# GasSensor.net
KiCad netlist of a schematic drawn in Altium Designer
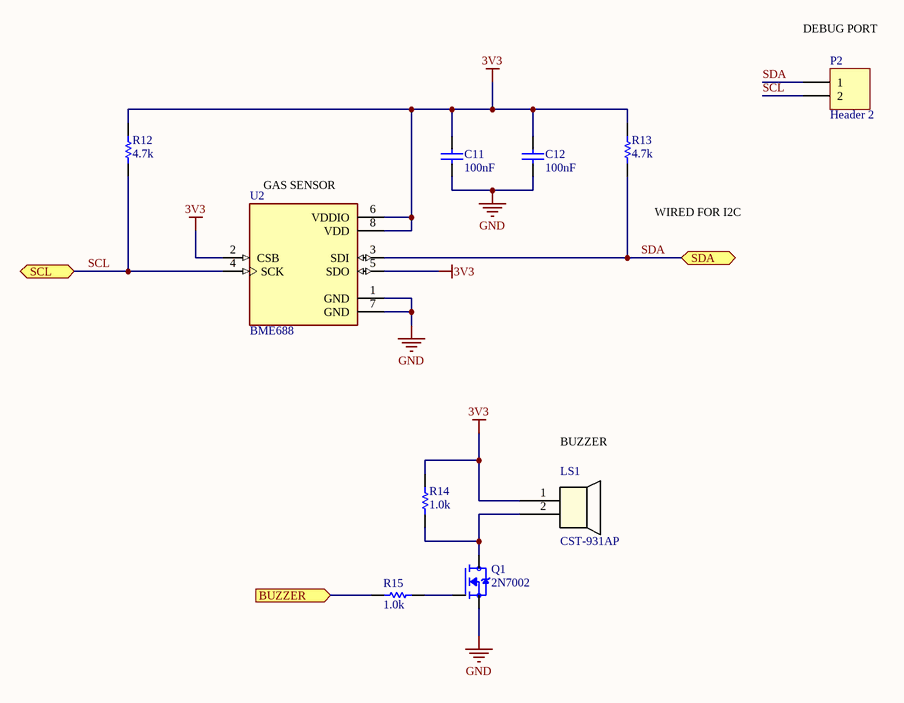
[diagram p0: GasSensor.SchDoc]

(export (version "E")
  (design (tool "Eeschema 10.0.6"))
  (components
    (comp (ref "C11")
      (value "100nF")
      (footprint "0402cap")
      (description "0402 Ceramic Chip Capacitor - Standard")
      (fields (field (name "Comment") "C0402"))
      (libsource (lib "Standard Components") (part "C0402"))
    )
    (comp (ref "C12")
      (value "100nF")
      (footprint "0402cap")
      (description "0402 Ceramic Chip Capacitor - Standard")
      (fields (field (name "Comment") "C0402"))
      (libsource (lib "Standard Components") (part "C0402"))
    )
    (comp (ref "LS1")
      (value "CST-931AP")
      (footprint "CST-931AP_CUD")
      (description "No Description Available")
      (libsource (lib "Buzzer") (part "CST-931AP"))
    )
    (comp (ref "P2")
      (value "Header 2")
      (footprint "HDR1X2")
      (description "Header, 2-Pin")
      (fields (field (name "PUBLISHER") "Altium Limited"))
      (libsource (lib "Miscellaneous Connectors") (part "Header 2"))
    )
    (comp (ref "Q1")
      (value "2N7002")
      (footprint "SOT95P240X111-3N")
      (description "N-Channel 60V 280mA (Ta) 350mW (Ta) Surface Mount SOT-23-3 (TO-236)")
      (fields (field (name "MP") "altium_native_batch"))
      (libsource (lib "2N7002") (part "2N7002"))
    )
    (comp (ref "R12")
      (value "4.7k")
      (footprint "0402RES")
      (description "0402 Chip Resistor - Standard")
      (fields (field (name "Comment") "R0402"))
      (libsource (lib "Standard Components") (part "R0402"))
    )
    (comp (ref "R13")
      (value "4.7k")
      (footprint "0402RES")
      (description "0402 Chip Resistor - Standard")
      (fields (field (name "Comment") "R0402"))
      (libsource (lib "Standard Components") (part "R0402"))
    )
    (comp (ref "R14")
      (value "1.0k")
      (footprint "0805RES")
      (description "0805 Chip Resistor - Standard")
      (fields (field (name "Comment") "R0805"))
      (libsource (lib "Standard Components") (part "R0805"))
    )
    (comp (ref "R15")
      (value "1.0k")
      (footprint "0402RES")
      (description "0402 Chip Resistor - Standard")
      (fields (field (name "Comment") "R0402"))
      (libsource (lib "Standard Components") (part "R0402"))
    )
    (comp (ref "U2")
      (value "BME688")
      (footprint "IC_BME688")
      (description "Gas sensor measuring relative humidity, barometric pressure, ambient temperature and gas (VOC)")
      (libsource (lib "BME688") (part "BME688"))
    )
  )
  (nets
    (net (code "1") (name "/BUZZER") (class "Default")
      (node (ref "R15") (pin "2") (pinfunction "2_2") (pintype "passive"))
    )
    (net (code "2") (name "/SCL") (class "Default")
      (node (ref "P2") (pin "2") (pinfunction "2_2") (pintype "passive"))
      (node (ref "R12") (pin "1") (pinfunction "1_1") (pintype "passive"))
      (node (ref "U2") (pin "4") (pinfunction "SCK_4") (pintype "input"))
    )
    (net (code "3") (name "/SDA") (class "Default")
      (node (ref "P2") (pin "1") (pinfunction "1_1") (pintype "passive"))
      (node (ref "R13") (pin "1") (pinfunction "1_1") (pintype "passive"))
      (node (ref "U2") (pin "3") (pinfunction "SDI_3") (pintype "bidirectional"))
    )
    (net (code "4") (name "3V3") (class "Default")
      (node (ref "C11") (pin "2") (pinfunction "2_2") (pintype "passive"))
      (node (ref "C12") (pin "2") (pinfunction "2_2") (pintype "passive"))
      (node (ref "LS1") (pin "1") (pinfunction "1_1") (pintype "passive"))
      (node (ref "R12") (pin "2") (pinfunction "2_2") (pintype "passive"))
      (node (ref "R13") (pin "2") (pinfunction "2_2") (pintype "passive"))
      (node (ref "R14") (pin "2") (pinfunction "2_2") (pintype "passive"))
      (node (ref "U2") (pin "2") (pinfunction "CSB_2") (pintype "input"))
      (node (ref "U2") (pin "5") (pinfunction "SDO_5") (pintype "bidirectional"))
      (node (ref "U2") (pin "6") (pinfunction "VDDIO_6") (pintype "power_in"))
      (node (ref "U2") (pin "8") (pinfunction "VDD_8") (pintype "power_in"))
    )
    (net (code "5") (name "GND") (class "Default")
      (node (ref "C11") (pin "1") (pinfunction "1_1") (pintype "passive"))
      (node (ref "C12") (pin "1") (pinfunction "1_1") (pintype "passive"))
      (node (ref "Q1") (pin "2") (pinfunction "S_2") (pintype "passive"))
      (node (ref "U2") (pin "1") (pinfunction "GND_1") (pintype "power_in"))
      (node (ref "U2") (pin "7") (pinfunction "GND_7") (pintype "power_in"))
    )
    (net (code "6") (name "Net-(Q1-D)") (class "Default")
      (node (ref "LS1") (pin "2") (pinfunction "2_2") (pintype "passive"))
      (node (ref "Q1") (pin "3") (pinfunction "D_3") (pintype "passive"))
      (node (ref "R14") (pin "1") (pinfunction "1_1") (pintype "passive"))
    )
    (net (code "7") (name "Net-(Q1-G)") (class "Default")
      (node (ref "Q1") (pin "1") (pinfunction "G_1") (pintype "passive"))
      (node (ref "R15") (pin "1") (pinfunction "1_1") (pintype "passive"))
    )
  )
)
